# Wattuino-Pro-Mini-PB_v10.net
KiCad netlist of a schematic drawn in EAGLE
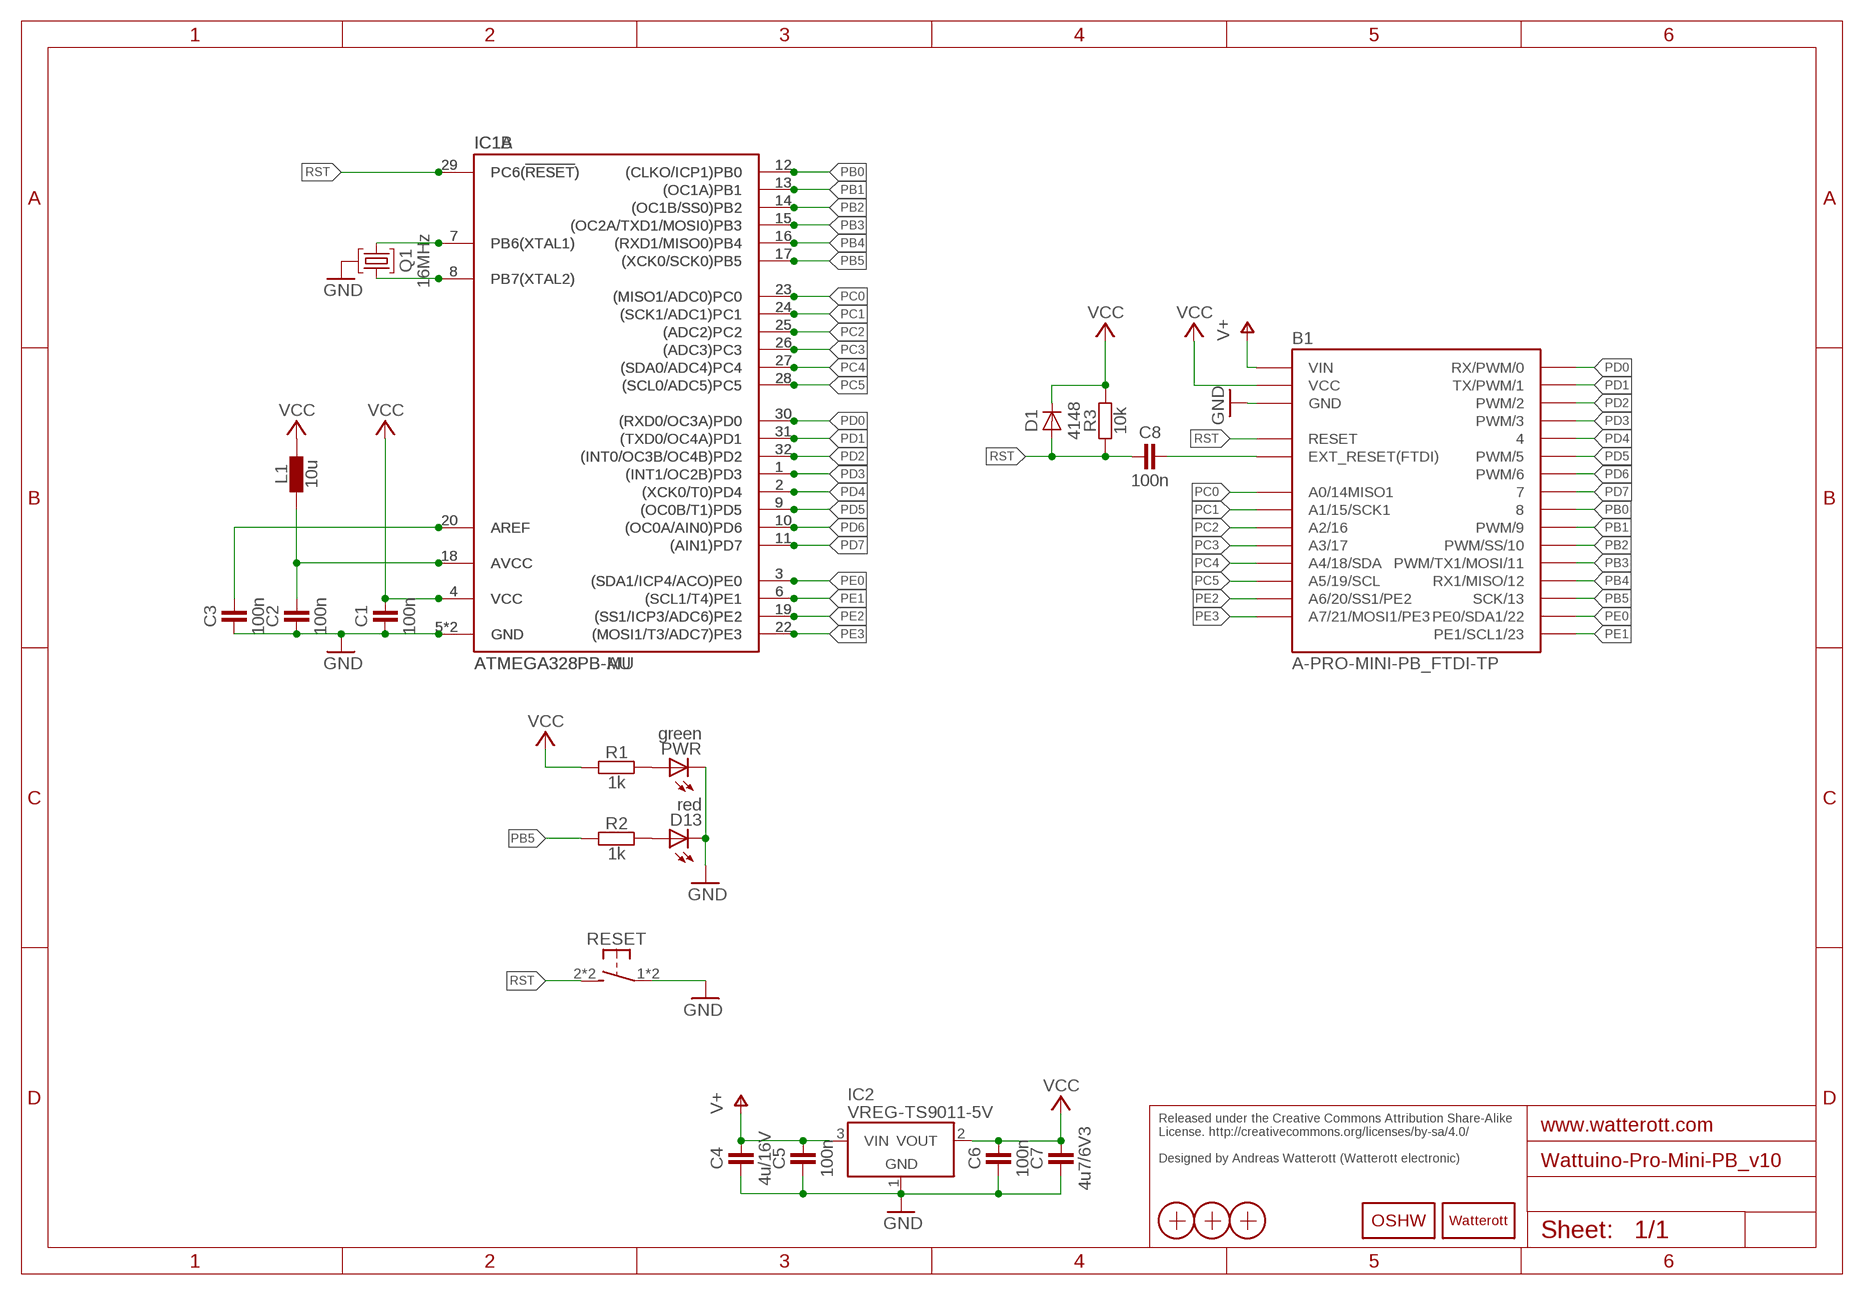
[diagram p0: schematic, sheet 1]

(export (version "E")
  (design (tool "Eeschema 10.0.6"))
  (components
    (comp (ref "B1")
      (value "A-PRO-MINI-PB_FTDI-TP")
      (footprint "eagle-import:A-PRO-MINI-PB-FTDI_TP")
      (libsource (lib "eagle-import") (part "A-PRO-MINI-PB_FTDI-TP"))
    )
    (comp (ref "C1")
      (value "100n")
      (footprint "eagle-import:C0402")
      (libsource (lib "eagle-import") (part "CAPACITOR-0402"))
    )
    (comp (ref "C2")
      (value "100n")
      (footprint "eagle-import:C0402")
      (libsource (lib "eagle-import") (part "CAPACITOR-0402"))
    )
    (comp (ref "C3")
      (value "100n")
      (footprint "eagle-import:C0402")
      (libsource (lib "eagle-import") (part "CAPACITOR-0402"))
    )
    (comp (ref "C4")
      (value "4u/16V")
      (footprint "eagle-import:C0805")
      (libsource (lib "eagle-import") (part "CAPACITOR-0805"))
    )
    (comp (ref "C5")
      (value "100n")
      (footprint "eagle-import:C0402")
      (libsource (lib "eagle-import") (part "CAPACITOR-0402"))
    )
    (comp (ref "C6")
      (value "100n")
      (footprint "eagle-import:C0402")
      (libsource (lib "eagle-import") (part "CAPACITOR-0402"))
    )
    (comp (ref "C7")
      (value "4u7/6V3")
      (footprint "eagle-import:C0402")
      (libsource (lib "eagle-import") (part "CAPACITOR-0402"))
    )
    (comp (ref "C8")
      (value "100n")
      (footprint "eagle-import:C0402")
      (libsource (lib "eagle-import") (part "CAPACITOR-0402"))
    )
    (comp (ref "D1")
      (value "4148")
      (footprint "eagle-import:SOD882")
      (libsource (lib "eagle-import") (part "DIODE-SOD882"))
    )
    (comp (ref "D13")
      (value "red")
      (footprint "eagle-import:C0603")
      (libsource (lib "eagle-import") (part "LED-0603"))
    )
    (comp (ref "IC1A")
      (value "ATMEGA328PB-AU")
      (footprint "eagle-import:TQFP32")
      (libsource (lib "eagle-import") (part "ATMEGA328PB-AU"))
    )
    (comp (ref "IC1B")
      (value "ATMEGA328PB-MU")
      (footprint "eagle-import:QFN32-PAD")
      (libsource (lib "eagle-import") (part "ATMEGA328PB-MU"))
    )
    (comp (ref "IC2")
      (value "VREG-TS9011-5V")
      (footprint "eagle-import:SOT23")
      (libsource (lib "eagle-import") (part "VREG-TS9011-5V"))
    )
    (comp (ref "L1")
      (value "10u")
      (footprint "eagle-import:C0603")
      (libsource (lib "eagle-import") (part "INDUCTOR-0603"))
    )
    (comp (ref "LOGO1")
      (value "OSHW_LOGOX0070")
      (footprint "eagle-import:OSHW_6X70")
      (libsource (lib "eagle-import") (part "OSHW_LOGOX0070"))
    )
    (comp (ref "LOGO2")
      (value "LOGO-S_PLACE_S")
      (footprint "eagle-import:SPARK_TPLACE_S")
      (libsource (lib "eagle-import") (part "LOGO-S_PLACE_S"))
    )
    (comp (ref "PWR")
      (value "green")
      (footprint "eagle-import:C0603")
      (libsource (lib "eagle-import") (part "LED-0603"))
    )
    (comp (ref "Q1")
      (value "16MHz")
      (footprint "eagle-import:CRYSTAL_32X13")
      (libsource (lib "eagle-import") (part "CRYSTAL-RES-32"))
    )
    (comp (ref "R1")
      (value "1k")
      (footprint "eagle-import:C0402")
      (libsource (lib "eagle-import") (part "RESISTOR-0402"))
    )
    (comp (ref "R2")
      (value "1k")
      (footprint "eagle-import:C0402")
      (libsource (lib "eagle-import") (part "RESISTOR-0402"))
    )
    (comp (ref "R3")
      (value "10k")
      (footprint "eagle-import:C0402")
      (libsource (lib "eagle-import") (part "RESISTOR-0402"))
    )
    (comp (ref "RESET")
      (value "SW-TACTILE-TL3315")
      (footprint "eagle-import:TL3315N")
      (libsource (lib "eagle-import") (part "SW-TACTILE-TL3315"))
    )
    (comp (ref "X1")
      (value "PASSER-07")
      (footprint "eagle-import:PASSER_07MM")
      (libsource (lib "eagle-import") (part "PASSER-07"))
    )
    (comp (ref "X2")
      (value "PASSER-07")
      (footprint "eagle-import:PASSER_07MM")
      (libsource (lib "eagle-import") (part "PASSER-07"))
    )
    (comp (ref "X3")
      (value "PASSER-07")
      (footprint "eagle-import:PASSER_07MM")
      (libsource (lib "eagle-import") (part "PASSER-07"))
    )
  )
  (nets
    (net (code "1") (name "GND") (class "Default")
      (node (ref "B1") (pin "GND@1") (pinfunction "GND_GND@1") (pintype "power_in"))
      (node (ref "B1") (pin "GND@2") (pinfunction "GND_GND@2") (pintype "power_in"))
      (node (ref "B1") (pin "GND@3") (pinfunction "GND_GND@3") (pintype "power_in"))
      (node (ref "B1") (pin "GND@4") (pinfunction "GND_GND@4") (pintype "power_in"))
      (node (ref "C1") (pin "1") (pinfunction "1_1") (pintype "passive"))
      (node (ref "C2") (pin "1") (pinfunction "1_1") (pintype "passive"))
      (node (ref "C3") (pin "1") (pinfunction "1_1") (pintype "passive"))
      (node (ref "C4") (pin "1") (pinfunction "1_1") (pintype "passive"))
      (node (ref "C5") (pin "1") (pinfunction "1_1") (pintype "passive"))
      (node (ref "C6") (pin "1") (pinfunction "1_1") (pintype "passive"))
      (node (ref "C7") (pin "1") (pinfunction "1_1") (pintype "passive"))
      (node (ref "D13") (pin "C") (pinfunction "C_C") (pintype "passive"))
      (node (ref "IC1A") (pin "21") (pinfunction "GND_21") (pintype "power_in"))
      (node (ref "IC1A") (pin "5") (pinfunction "GND_5") (pintype "power_in"))
      (node (ref "IC1B") (pin "21") (pinfunction "GND_21") (pintype "power_in"))
      (node (ref "IC1B") (pin "5") (pinfunction "GND_5") (pintype "power_in"))
      (node (ref "IC2") (pin "1") (pinfunction "GND_1") (pintype "power_in"))
      (node (ref "PWR") (pin "C") (pinfunction "C_C") (pintype "passive"))
      (node (ref "Q1") (pin "GND") (pinfunction "GND_GND") (pintype "passive"))
      (node (ref "RESET") (pin "1") (pinfunction "P1_1") (pintype "passive"))
      (node (ref "RESET") (pin "4") (pinfunction "P1_4") (pintype "passive"))
    )
    (net (code "2") (name "Net-(B1-EXT_RESET(FTDI))") (class "Default")
      (node (ref "B1") (pin "EXT_RST") (pinfunction "EXT_RESET(FTDI)_EXT_RST") (pintype "bidirectional"))
      (node (ref "C8") (pin "2") (pinfunction "2_2") (pintype "passive"))
    )
    (net (code "3") (name "Net-(D13-PadA)") (class "Default")
      (node (ref "D13") (pin "A") (pinfunction "A_A") (pintype "passive"))
      (node (ref "R2") (pin "2") (pinfunction "2_2") (pintype "passive"))
    )
    (net (code "4") (name "Net-(IC1A-AREF)") (class "Default")
      (node (ref "C3") (pin "2") (pinfunction "2_2") (pintype "passive"))
      (node (ref "IC1A") (pin "20") (pinfunction "AREF_20") (pintype "passive"))
      (node (ref "IC1B") (pin "20") (pinfunction "AREF_20") (pintype "passive"))
    )
    (net (code "5") (name "Net-(IC1A-AVCC)") (class "Default")
      (node (ref "C2") (pin "2") (pinfunction "2_2") (pintype "passive"))
      (node (ref "IC1A") (pin "18") (pinfunction "AVCC_18") (pintype "power_in"))
      (node (ref "IC1B") (pin "18") (pinfunction "AVCC_18") (pintype "power_in"))
      (node (ref "L1") (pin "1") (pinfunction "1_1") (pintype "passive"))
    )
    (net (code "6") (name "Net-(IC1A-PB6(XTAL1))") (class "Default")
      (node (ref "IC1A") (pin "7") (pinfunction "PB6(XTAL1)_7") (pintype "bidirectional"))
      (node (ref "IC1B") (pin "7") (pinfunction "PB6(XTAL1)_7") (pintype "bidirectional"))
      (node (ref "Q1") (pin "2") (pinfunction "2_2") (pintype "passive"))
    )
    (net (code "7") (name "Net-(IC1A-PB7(XTAL2))") (class "Default")
      (node (ref "IC1A") (pin "8") (pinfunction "PB7(XTAL2)_8") (pintype "bidirectional"))
      (node (ref "IC1B") (pin "8") (pinfunction "PB7(XTAL2)_8") (pintype "bidirectional"))
      (node (ref "Q1") (pin "1") (pinfunction "1_1") (pintype "passive"))
    )
    (net (code "8") (name "Net-(PWR-PadA)") (class "Default")
      (node (ref "PWR") (pin "A") (pinfunction "A_A") (pintype "passive"))
      (node (ref "R1") (pin "2") (pinfunction "2_2") (pintype "passive"))
    )
    (net (code "9") (name "PB0") (class "Default")
      (node (ref "B1") (pin "8") (pinfunction "8_8") (pintype "bidirectional"))
      (node (ref "IC1A") (pin "12") (pinfunction "(CLKO/ICP1)PB0_12") (pintype "bidirectional"))
      (node (ref "IC1B") (pin "12") (pinfunction "(CLKO/ICP1)PB0_12") (pintype "bidirectional"))
    )
    (net (code "10") (name "PB1") (class "Default")
      (node (ref "B1") (pin "9") (pinfunction "PWM/9_9") (pintype "bidirectional"))
      (node (ref "IC1A") (pin "13") (pinfunction "(OC1A)PB1_13") (pintype "bidirectional"))
      (node (ref "IC1B") (pin "13") (pinfunction "(OC1A)PB1_13") (pintype "bidirectional"))
    )
    (net (code "11") (name "PB2") (class "Default")
      (node (ref "B1") (pin "10") (pinfunction "PWM/SS/10_10") (pintype "bidirectional"))
      (node (ref "IC1A") (pin "14") (pinfunction "(OC1B/SS0)PB2_14") (pintype "bidirectional"))
      (node (ref "IC1B") (pin "14") (pinfunction "(OC1B/SS0)PB2_14") (pintype "bidirectional"))
    )
    (net (code "12") (name "PB3") (class "Default")
      (node (ref "B1") (pin "11") (pinfunction "PWM/TX1/MOSI/11_11") (pintype "bidirectional"))
      (node (ref "IC1A") (pin "15") (pinfunction "(OC2A/TXD1/MOSI0)PB3_15") (pintype "bidirectional"))
      (node (ref "IC1B") (pin "15") (pinfunction "(OC2A/TXD1/MOSI0)PB3_15") (pintype "bidirectional"))
    )
    (net (code "13") (name "PB4") (class "Default")
      (node (ref "B1") (pin "12") (pinfunction "RX1/MISO/12_12") (pintype "bidirectional"))
      (node (ref "IC1A") (pin "16") (pinfunction "(RXD1/MISO0)PB4_16") (pintype "bidirectional"))
      (node (ref "IC1B") (pin "16") (pinfunction "(RXD1/MISO0)PB4_16") (pintype "bidirectional"))
    )
    (net (code "14") (name "PB5") (class "Default")
      (node (ref "B1") (pin "13") (pinfunction "SCK/13_13") (pintype "bidirectional"))
      (node (ref "IC1A") (pin "17") (pinfunction "(XCK0/SCK0)PB5_17") (pintype "bidirectional"))
      (node (ref "IC1B") (pin "17") (pinfunction "(XCK0/SCK0)PB5_17") (pintype "bidirectional"))
      (node (ref "R2") (pin "1") (pinfunction "1_1") (pintype "passive"))
    )
    (net (code "15") (name "PC0") (class "Default")
      (node (ref "B1") (pin "A0") (pinfunction "A0/14MISO1_A0") (pintype "bidirectional"))
      (node (ref "IC1A") (pin "23") (pinfunction "(MISO1/ADC0)PC0_23") (pintype "bidirectional"))
      (node (ref "IC1B") (pin "23") (pinfunction "(MISO1/ADC0)PC0_23") (pintype "bidirectional"))
    )
    (net (code "16") (name "PC1") (class "Default")
      (node (ref "B1") (pin "A1") (pinfunction "A1/15/SCK1_A1") (pintype "bidirectional"))
      (node (ref "IC1A") (pin "24") (pinfunction "(SCK1/ADC1)PC1_24") (pintype "bidirectional"))
      (node (ref "IC1B") (pin "24") (pinfunction "(SCK1/ADC1)PC1_24") (pintype "bidirectional"))
    )
    (net (code "17") (name "PC2") (class "Default")
      (node (ref "B1") (pin "A2") (pinfunction "A2/16_A2") (pintype "bidirectional"))
      (node (ref "IC1A") (pin "25") (pinfunction "(ADC2)PC2_25") (pintype "bidirectional"))
      (node (ref "IC1B") (pin "25") (pinfunction "(ADC2)PC2_25") (pintype "bidirectional"))
    )
    (net (code "18") (name "PC3") (class "Default")
      (node (ref "B1") (pin "A3") (pinfunction "A3/17_A3") (pintype "bidirectional"))
      (node (ref "IC1A") (pin "26") (pinfunction "(ADC3)PC3_26") (pintype "bidirectional"))
      (node (ref "IC1B") (pin "26") (pinfunction "(ADC3)PC3_26") (pintype "bidirectional"))
    )
    (net (code "19") (name "PC4") (class "Default")
      (node (ref "B1") (pin "A4") (pinfunction "A4/18/SDA_A4") (pintype "bidirectional"))
      (node (ref "IC1A") (pin "27") (pinfunction "(SDA0/ADC4)PC4_27") (pintype "bidirectional"))
      (node (ref "IC1B") (pin "27") (pinfunction "(SDA0/ADC4)PC4_27") (pintype "bidirectional"))
    )
    (net (code "20") (name "PC5") (class "Default")
      (node (ref "B1") (pin "A5") (pinfunction "A5/19/SCL_A5") (pintype "bidirectional"))
      (node (ref "IC1A") (pin "28") (pinfunction "(SCL0/ADC5)PC5_28") (pintype "bidirectional"))
      (node (ref "IC1B") (pin "28") (pinfunction "(SCL0/ADC5)PC5_28") (pintype "bidirectional"))
    )
    (net (code "21") (name "PD0") (class "Default")
      (node (ref "B1") (pin "RXD@1") (pinfunction "RX/PWM/0_RXD@1") (pintype "bidirectional"))
      (node (ref "B1") (pin "RXD@2") (pinfunction "RX/PWM/0_RXD@2") (pintype "bidirectional"))
      (node (ref "IC1A") (pin "30") (pinfunction "(RXD0/OC3A)PD0_30") (pintype "bidirectional"))
      (node (ref "IC1B") (pin "30") (pinfunction "(RXD0/OC3A)PD0_30") (pintype "bidirectional"))
    )
    (net (code "22") (name "PD1") (class "Default")
      (node (ref "B1") (pin "TXD@1") (pinfunction "TX/PWM/1_TXD@1") (pintype "bidirectional"))
      (node (ref "B1") (pin "TXD@2") (pinfunction "TX/PWM/1_TXD@2") (pintype "bidirectional"))
      (node (ref "IC1A") (pin "31") (pinfunction "(TXD0/OC4A)PD1_31") (pintype "bidirectional"))
      (node (ref "IC1B") (pin "31") (pinfunction "(TXD0/OC4A)PD1_31") (pintype "bidirectional"))
    )
    (net (code "23") (name "PD2") (class "Default")
      (node (ref "B1") (pin "2") (pinfunction "PWM/2_2") (pintype "bidirectional"))
      (node (ref "IC1A") (pin "32") (pinfunction "(INT0/OC3B/OC4B)PD2_32") (pintype "bidirectional"))
      (node (ref "IC1B") (pin "32") (pinfunction "(INT0/OC3B/OC4B)PD2_32") (pintype "bidirectional"))
    )
    (net (code "24") (name "PD3") (class "Default")
      (node (ref "B1") (pin "3") (pinfunction "PWM/3_3") (pintype "bidirectional"))
      (node (ref "IC1A") (pin "1") (pinfunction "(INT1/OC2B)PD3_1") (pintype "bidirectional"))
      (node (ref "IC1B") (pin "1") (pinfunction "(INT1/OC2B)PD3_1") (pintype "bidirectional"))
    )
    (net (code "25") (name "PD4") (class "Default")
      (node (ref "B1") (pin "4") (pinfunction "4_4") (pintype "bidirectional"))
      (node (ref "IC1A") (pin "2") (pinfunction "(XCK0/T0)PD4_2") (pintype "bidirectional"))
      (node (ref "IC1B") (pin "2") (pinfunction "(XCK0/T0)PD4_2") (pintype "bidirectional"))
    )
    (net (code "26") (name "PD5") (class "Default")
      (node (ref "B1") (pin "5") (pinfunction "PWM/5_5") (pintype "bidirectional"))
      (node (ref "IC1A") (pin "9") (pinfunction "(OC0B/T1)PD5_9") (pintype "bidirectional"))
      (node (ref "IC1B") (pin "9") (pinfunction "(OC0B/T1)PD5_9") (pintype "bidirectional"))
    )
    (net (code "27") (name "PD6") (class "Default")
      (node (ref "B1") (pin "6") (pinfunction "PWM/6_6") (pintype "bidirectional"))
      (node (ref "IC1A") (pin "10") (pinfunction "(OC0A/AIN0)PD6_10") (pintype "bidirectional"))
      (node (ref "IC1B") (pin "10") (pinfunction "(OC0A/AIN0)PD6_10") (pintype "bidirectional"))
    )
    (net (code "28") (name "PD7") (class "Default")
      (node (ref "B1") (pin "7") (pinfunction "7_7") (pintype "bidirectional"))
      (node (ref "IC1A") (pin "11") (pinfunction "(AIN1)PD7_11") (pintype "bidirectional"))
      (node (ref "IC1B") (pin "11") (pinfunction "(AIN1)PD7_11") (pintype "bidirectional"))
    )
    (net (code "29") (name "PE0") (class "Default")
      (node (ref "B1") (pin "PE0") (pinfunction "PE0/SDA1/22_PE0") (pintype "bidirectional"))
      (node (ref "IC1A") (pin "3") (pinfunction "(SDA1/ICP4/ACO)PE0_3") (pintype "bidirectional"))
      (node (ref "IC1B") (pin "3") (pinfunction "(SDA1/ICP4/ACO)PE0_3") (pintype "bidirectional"))
    )
    (net (code "30") (name "PE1") (class "Default")
      (node (ref "B1") (pin "PE1") (pinfunction "PE1/SCL1/23_PE1") (pintype "bidirectional"))
      (node (ref "IC1A") (pin "6") (pinfunction "(SCL1/T4)PE1_6") (pintype "bidirectional"))
      (node (ref "IC1B") (pin "6") (pinfunction "(SCL1/T4)PE1_6") (pintype "bidirectional"))
    )
    (net (code "31") (name "PE2") (class "Default")
      (node (ref "B1") (pin "A6") (pinfunction "A6/20/SS1/PE2_A6") (pintype "bidirectional"))
      (node (ref "IC1A") (pin "19") (pinfunction "(SS1/ICP3/ADC6)PE2_19") (pintype "bidirectional"))
      (node (ref "IC1B") (pin "19") (pinfunction "(SS1/ICP3/ADC6)PE2_19") (pintype "bidirectional"))
    )
    (net (code "32") (name "PE3") (class "Default")
      (node (ref "B1") (pin "A7") (pinfunction "A7/21/MOSI1/PE3_A7") (pintype "bidirectional"))
      (node (ref "IC1A") (pin "22") (pinfunction "(MOSI1/T3/ADC7)PE3_22") (pintype "bidirectional"))
      (node (ref "IC1B") (pin "22") (pinfunction "(MOSI1/T3/ADC7)PE3_22") (pintype "bidirectional"))
    )
    (net (code "33") (name "RST") (class "Default")
      (node (ref "B1") (pin "RST@1") (pinfunction "RESET_RST@1") (pintype "bidirectional"))
      (node (ref "B1") (pin "RST@2") (pinfunction "RESET_RST@2") (pintype "bidirectional"))
      (node (ref "C8") (pin "1") (pinfunction "1_1") (pintype "passive"))
      (node (ref "D1") (pin "A") (pinfunction "A_A") (pintype "passive"))
      (node (ref "IC1A") (pin "29") (pinfunction "PC6(~{RESET})_29") (pintype "bidirectional"))
      (node (ref "IC1B") (pin "29") (pinfunction "PC6(~{RESET})_29") (pintype "bidirectional"))
      (node (ref "R3") (pin "1") (pinfunction "1_1") (pintype "passive"))
      (node (ref "RESET") (pin "2") (pinfunction "S1_2") (pintype "passive"))
      (node (ref "RESET") (pin "3") (pinfunction "S1_3") (pintype "passive"))
    )
    (net (code "34") (name "V+") (class "Default")
      (node (ref "B1") (pin "VIN") (pinfunction "VIN_VIN") (pintype "power_in"))
      (node (ref "C4") (pin "2") (pinfunction "2_2") (pintype "passive"))
      (node (ref "C5") (pin "2") (pinfunction "2_2") (pintype "passive"))
      (node (ref "IC2") (pin "3") (pinfunction "VIN_3") (pintype "power_in"))
    )
    (net (code "35") (name "VCC") (class "Default")
      (node (ref "B1") (pin "VCC@1") (pinfunction "VCC_VCC@1") (pintype "power_in"))
      (node (ref "B1") (pin "VCC@2") (pinfunction "VCC_VCC@2") (pintype "power_in"))
      (node (ref "C1") (pin "2") (pinfunction "2_2") (pintype "passive"))
      (node (ref "C6") (pin "2") (pinfunction "2_2") (pintype "passive"))
      (node (ref "C7") (pin "2") (pinfunction "2_2") (pintype "passive"))
      (node (ref "D1") (pin "C") (pinfunction "C_C") (pintype "passive"))
      (node (ref "IC1A") (pin "4") (pinfunction "VCC_4") (pintype "power_in"))
      (node (ref "IC1B") (pin "4") (pinfunction "VCC_4") (pintype "power_in"))
      (node (ref "IC2") (pin "2") (pinfunction "VOUT_2") (pintype "power_in"))
      (node (ref "L1") (pin "2") (pinfunction "2_2") (pintype "passive"))
      (node (ref "R1") (pin "1") (pinfunction "1_1") (pintype "passive"))
      (node (ref "R3") (pin "2") (pinfunction "2_2") (pintype "passive"))
    )
  )
)
